# nintendac_mini.net
KiCad netlist of a schematic drawn in EAGLE
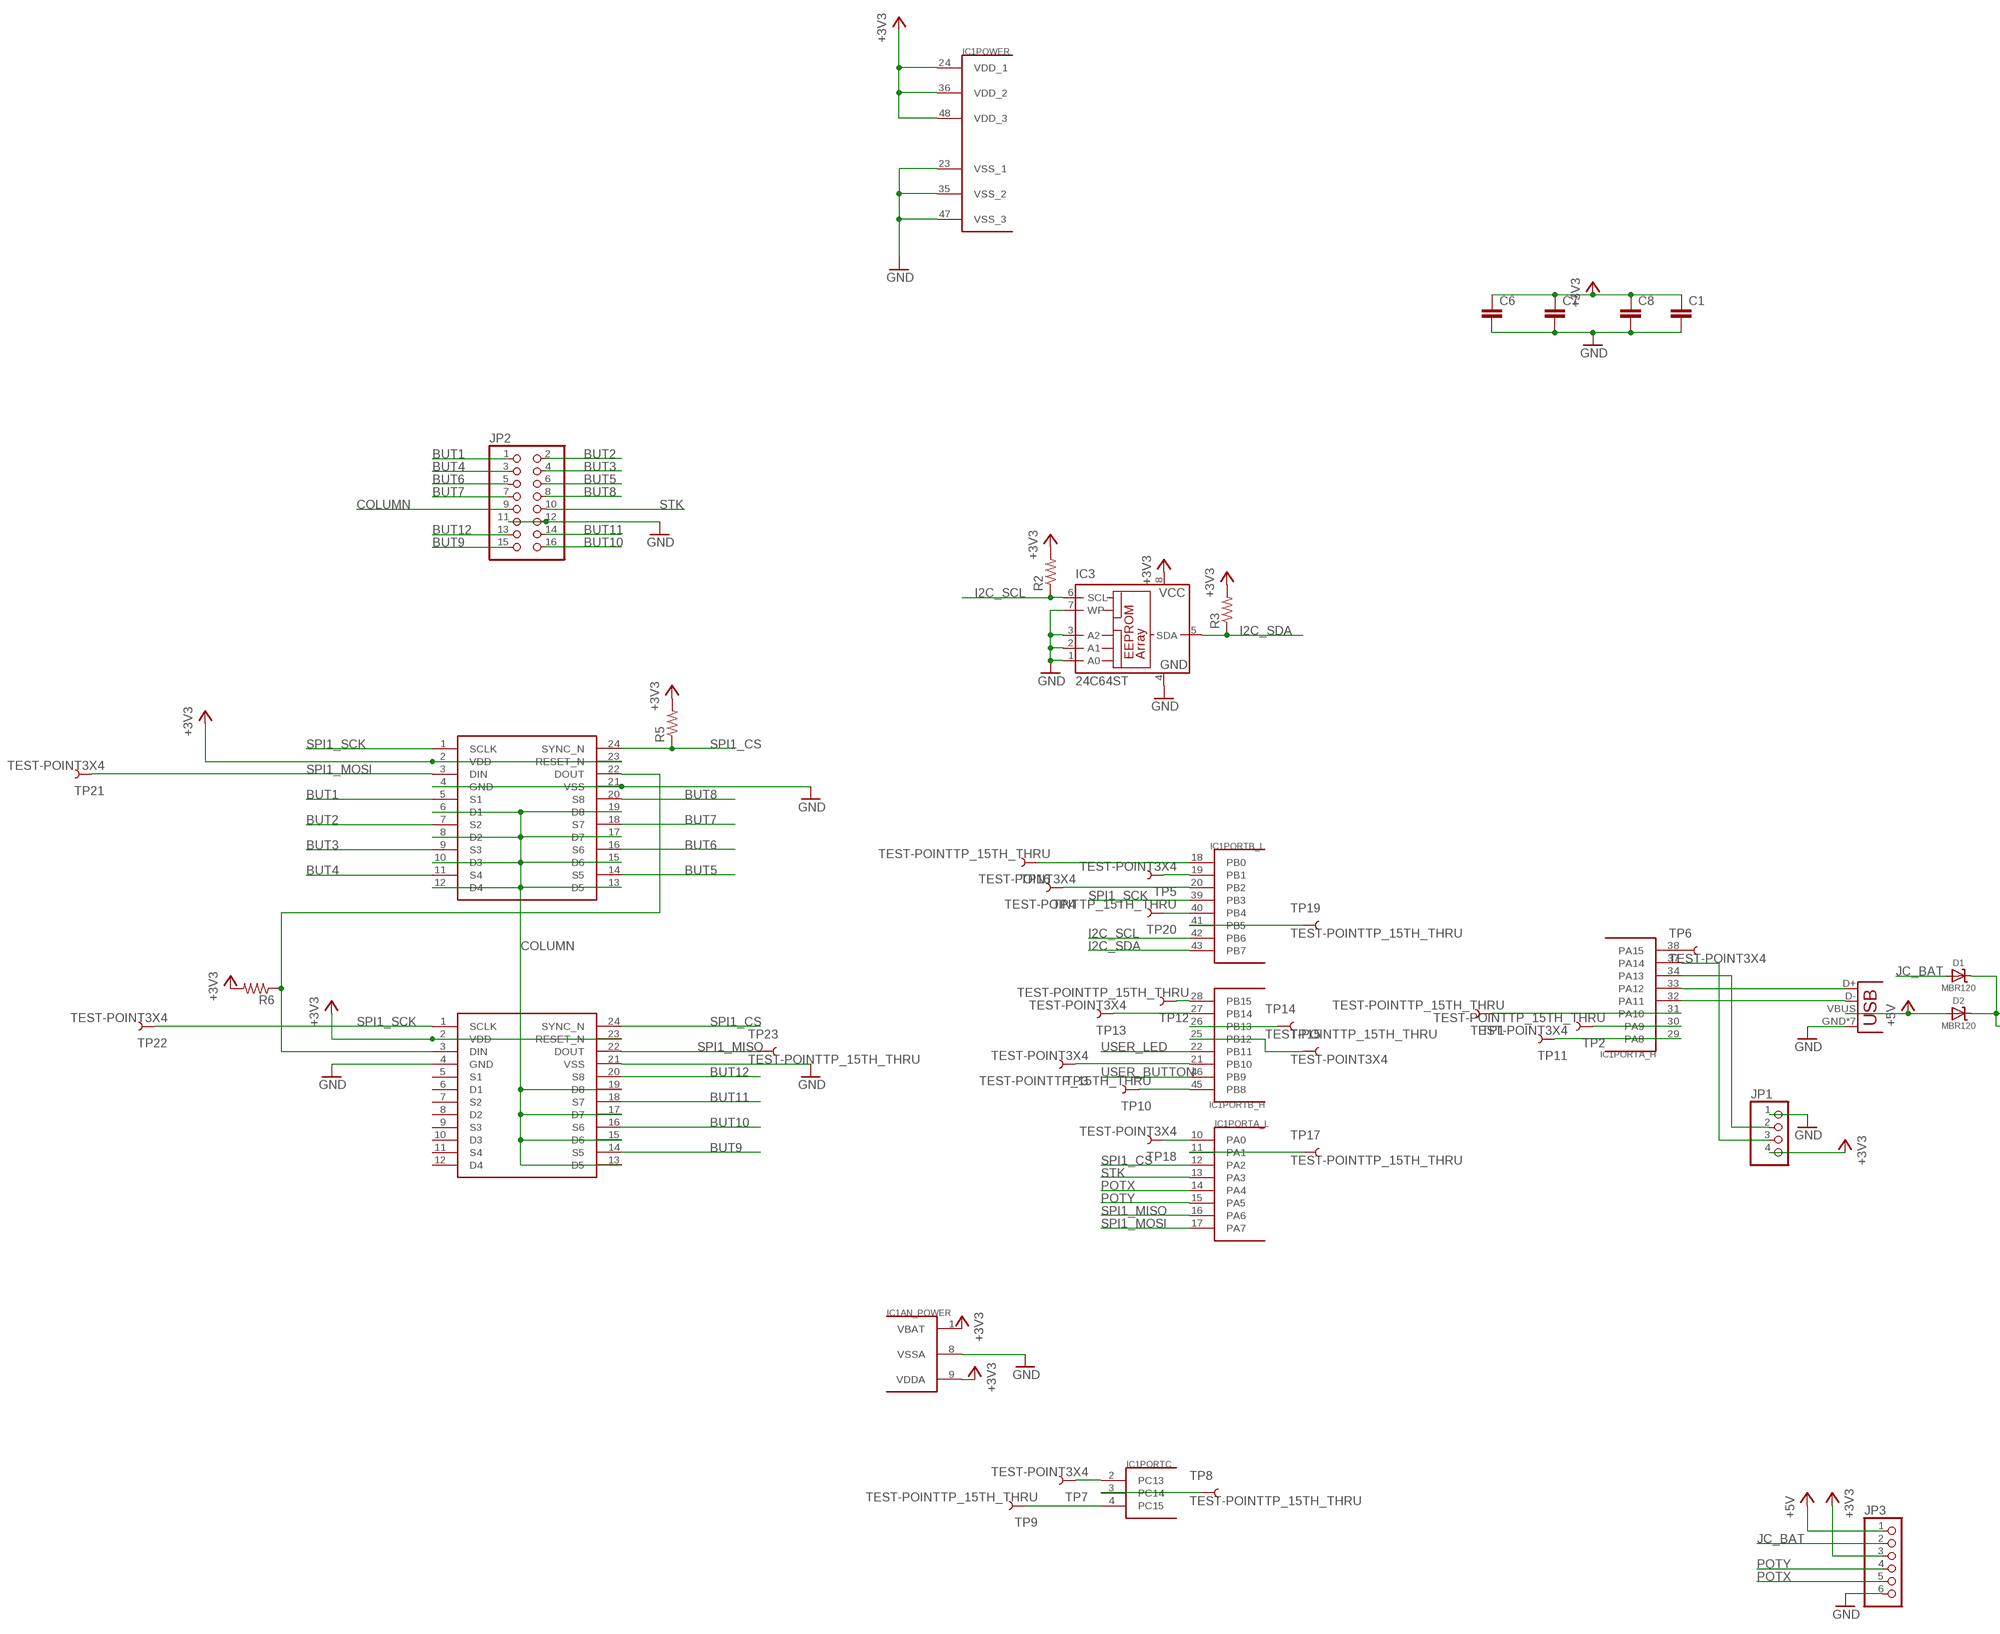
[diagram p0: schematic, sheet 1, part 1 of 2]
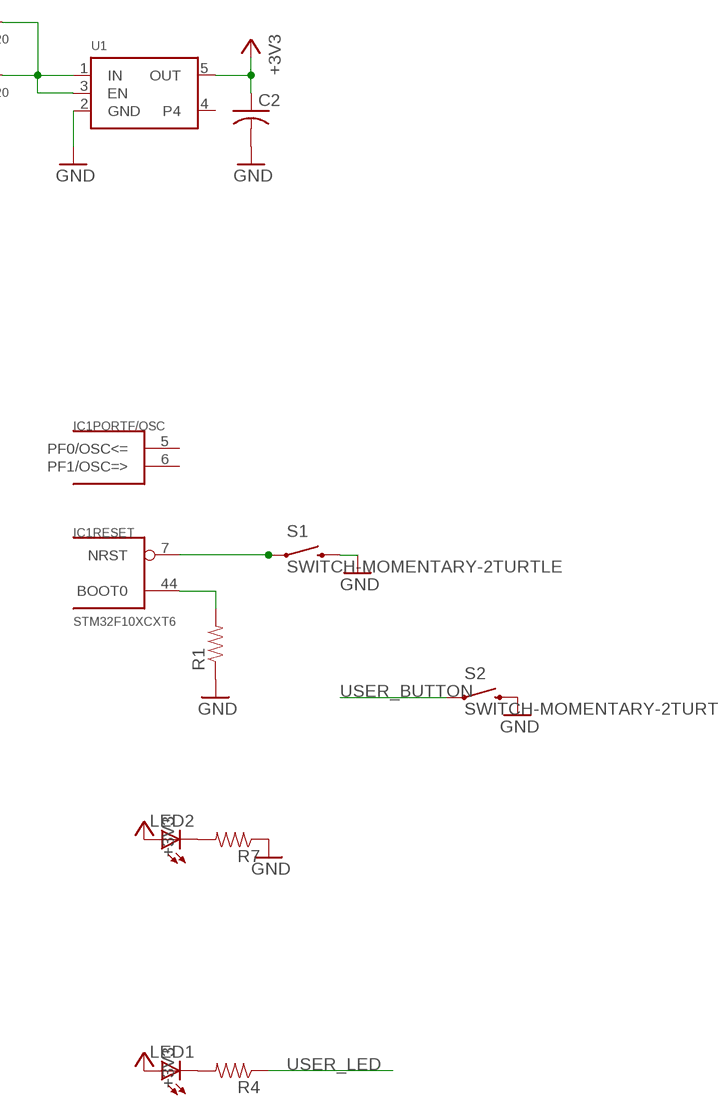
[diagram p1: schematic, sheet 1, part 2 of 2]

(export (version "E")
  (design (tool "Eeschema 10.0.6"))
  (components
    (comp (ref "C1")
      (value "CAP0805")
      (footprint "eagle-import:0805")
      (libsource (lib "eagle-import") (part "CAP0805"))
    )
    (comp (ref "C2")
      (value "C-USC1210")
      (footprint "eagle-import:C1210")
      (libsource (lib "eagle-import") (part "C-USC1210"))
    )
    (comp (ref "C6")
      (value "CAP0805")
      (footprint "eagle-import:0805")
      (libsource (lib "eagle-import") (part "CAP0805"))
    )
    (comp (ref "C7")
      (value "CAP0805")
      (footprint "eagle-import:0805")
      (libsource (lib "eagle-import") (part "CAP0805"))
    )
    (comp (ref "C8")
      (value "CAP0805")
      (footprint "eagle-import:0805")
      (libsource (lib "eagle-import") (part "CAP0805"))
    )
    (comp (ref "D1")
      (value "MBR120")
      (footprint "eagle-import:SOD-123")
      (libsource (lib "eagle-import") (part "DIODE-SCHOTTKYSOD-123"))
    )
    (comp (ref "D2")
      (value "MBR120")
      (footprint "eagle-import:SOD-123")
      (libsource (lib "eagle-import") (part "DIODE-SCHOTTKYSOD-123"))
    )
    (comp (ref "IC1")
      (value "STM32F10XCXT6")
      (footprint "eagle-import:TQFP48")
      (libsource (lib "eagle-import") (part "STM32F10XCXT6"))
    )
    (comp (ref "IC3")
      (value "24C64ST")
      (footprint "eagle-import:TSSOP8")
      (fields (field (name "MPN") "CAT24C64YI-GT3"))
      (libsource (lib "eagle-import") (part "24STC64"))
    )
    (comp (ref "JP1")
      (value "PINHD-1X4")
      (footprint "eagle-import:1X04")
      (libsource (lib "eagle-import") (part "PINHD-1X4"))
    )
    (comp (ref "JP2")
      (value "PINHD-2X8")
      (footprint "eagle-import:2X08")
      (libsource (lib "eagle-import") (part "PINHD-2X8"))
    )
    (comp (ref "JP3")
      (value "PINHD-1X6CB")
      (footprint "eagle-import:1X06-CLEANBIG")
      (libsource (lib "eagle-import") (part "PINHD-1X6CB"))
    )
    (comp (ref "LED1")
      (value "LEDCHIP-LED0805")
      (footprint "eagle-import:CHIP-LED0805")
      (libsource (lib "eagle-import") (part "LEDCHIP-LED0805"))
    )
    (comp (ref "LED2")
      (value "LEDCHIP-LED0805")
      (footprint "eagle-import:CHIP-LED0805")
      (libsource (lib "eagle-import") (part "LEDCHIP-LED0805"))
    )
    (comp (ref "R1")
      (value "RESISTOR0805-RES")
      (footprint "eagle-import:0805")
      (libsource (lib "eagle-import") (part "RESISTOR0805-RES"))
    )
    (comp (ref "R2")
      (value "RESISTOR0805-RES")
      (footprint "eagle-import:0805")
      (libsource (lib "eagle-import") (part "RESISTOR0805-RES"))
    )
    (comp (ref "R3")
      (value "RESISTOR0805-RES")
      (footprint "eagle-import:0805")
      (libsource (lib "eagle-import") (part "RESISTOR0805-RES"))
    )
    (comp (ref "R4")
      (value "RESISTOR0805-RES")
      (footprint "eagle-import:0805")
      (libsource (lib "eagle-import") (part "RESISTOR0805-RES"))
    )
    (comp (ref "R5")
      (value "RESISTOR0805-RES")
      (footprint "eagle-import:0805")
      (libsource (lib "eagle-import") (part "RESISTOR0805-RES"))
    )
    (comp (ref "R6")
      (value "RESISTOR0805-RES")
      (footprint "eagle-import:0805")
      (libsource (lib "eagle-import") (part "RESISTOR0805-RES"))
    )
    (comp (ref "R7")
      (value "RESISTOR0805-RES")
      (footprint "eagle-import:0805")
      (libsource (lib "eagle-import") (part "RESISTOR0805-RES"))
    )
    (comp (ref "S1")
      (value "SWITCH-MOMENTARY-2TURTLE")
      (footprint "eagle-import:KMR2")
      (libsource (lib "eagle-import") (part "SWITCH-MOMENTARY-2TURTLE"))
    )
    (comp (ref "S2")
      (value "SWITCH-MOMENTARY-2TURTLE")
      (footprint "eagle-import:KMR2")
      (libsource (lib "eagle-import") (part "SWITCH-MOMENTARY-2TURTLE"))
    )
    (comp (ref "TP1")
      (value "TEST-POINTTP_15TH_THRU")
      (footprint "eagle-import:TP_15TH")
      (libsource (lib "eagle-import") (part "pth testpoint_TEST-POINTTP_15TH_THRU"))
    )
    (comp (ref "TP2")
      (value "TEST-POINTTP_15TH_THRU")
      (footprint "eagle-import:TP_15TH")
      (libsource (lib "eagle-import") (part "pth testpoint_TEST-POINTTP_15TH_THRU"))
    )
    (comp (ref "TP3")
      (value "TEST-POINT3X4")
      (footprint "eagle-import:PAD.03X.04")
      (libsource (lib "eagle-import") (part "TEST-POINT3X4"))
    )
    (comp (ref "TP4")
      (value "TEST-POINT3X4")
      (footprint "eagle-import:PAD.03X.04")
      (libsource (lib "eagle-import") (part "TEST-POINT3X4"))
    )
    (comp (ref "TP5")
      (value "TEST-POINT3X4")
      (footprint "eagle-import:PAD.03X.04")
      (libsource (lib "eagle-import") (part "TEST-POINT3X4"))
    )
    (comp (ref "TP6")
      (value "TEST-POINT3X4")
      (footprint "eagle-import:PAD.03X.04")
      (libsource (lib "eagle-import") (part "TEST-POINT3X4"))
    )
    (comp (ref "TP7")
      (value "TEST-POINT3X4")
      (footprint "eagle-import:PAD.03X.04")
      (libsource (lib "eagle-import") (part "TEST-POINT3X4"))
    )
    (comp (ref "TP8")
      (value "TEST-POINTTP_15TH_THRU")
      (footprint "eagle-import:TP_15TH")
      (libsource (lib "eagle-import") (part "pth testpoint_TEST-POINTTP_15TH_THRU"))
    )
    (comp (ref "TP9")
      (value "TEST-POINTTP_15TH_THRU")
      (footprint "eagle-import:TP_15TH")
      (libsource (lib "eagle-import") (part "pth testpoint_TEST-POINTTP_15TH_THRU"))
    )
    (comp (ref "TP10")
      (value "TEST-POINTTP_15TH_THRU")
      (footprint "eagle-import:TP_15TH")
      (libsource (lib "eagle-import") (part "pth testpoint_TEST-POINTTP_15TH_THRU"))
    )
    (comp (ref "TP11")
      (value "TEST-POINT3X4")
      (footprint "eagle-import:PAD.03X.04")
      (libsource (lib "eagle-import") (part "TEST-POINT3X4"))
    )
    (comp (ref "TP12")
      (value "TEST-POINTTP_15TH_THRU")
      (footprint "eagle-import:TP_15TH")
      (libsource (lib "eagle-import") (part "pth testpoint_TEST-POINTTP_15TH_THRU"))
    )
    (comp (ref "TP13")
      (value "TEST-POINT3X4")
      (footprint "eagle-import:PAD.03X.04")
      (libsource (lib "eagle-import") (part "TEST-POINT3X4"))
    )
    (comp (ref "TP14")
      (value "TEST-POINTTP_15TH_THRU")
      (footprint "eagle-import:TP_15TH")
      (libsource (lib "eagle-import") (part "pth testpoint_TEST-POINTTP_15TH_THRU"))
    )
    (comp (ref "TP15")
      (value "TEST-POINT3X4")
      (footprint "eagle-import:PAD.03X.04")
      (libsource (lib "eagle-import") (part "TEST-POINT3X4"))
    )
    (comp (ref "TP16")
      (value "TEST-POINTTP_15TH_THRU")
      (footprint "eagle-import:TP_15TH")
      (libsource (lib "eagle-import") (part "pth testpoint_TEST-POINTTP_15TH_THRU"))
    )
    (comp (ref "TP17")
      (value "TEST-POINTTP_15TH_THRU")
      (footprint "eagle-import:TP_15TH")
      (libsource (lib "eagle-import") (part "pth testpoint_TEST-POINTTP_15TH_THRU"))
    )
    (comp (ref "TP18")
      (value "TEST-POINT3X4")
      (footprint "eagle-import:PAD.03X.04")
      (libsource (lib "eagle-import") (part "TEST-POINT3X4"))
    )
    (comp (ref "TP19")
      (value "TEST-POINTTP_15TH_THRU")
      (footprint "eagle-import:TP_15TH")
      (libsource (lib "eagle-import") (part "pth testpoint_TEST-POINTTP_15TH_THRU"))
    )
    (comp (ref "TP20")
      (value "TEST-POINTTP_15TH_THRU")
      (footprint "eagle-import:TP_15TH")
      (libsource (lib "eagle-import") (part "pth testpoint_TEST-POINTTP_15TH_THRU"))
    )
    (comp (ref "TP21")
      (value "TEST-POINT3X4")
      (footprint "eagle-import:PAD.03X.04")
      (libsource (lib "eagle-import") (part "TEST-POINT3X4"))
    )
    (comp (ref "TP22")
      (value "TEST-POINT3X4")
      (footprint "eagle-import:PAD.03X.04")
      (libsource (lib "eagle-import") (part "TEST-POINT3X4"))
    )
    (comp (ref "TP23")
      (value "TEST-POINTTP_15TH_THRU")
      (footprint "eagle-import:TP_15TH")
      (libsource (lib "eagle-import") (part "pth testpoint_TEST-POINTTP_15TH_THRU"))
    )
    (comp (ref "U$3")
      (value "ADG714_DEV")
      (footprint "eagle-import:TSSOP-24")
      (libsource (lib "eagle-import") (part "ADG714_DEV"))
    )
    (comp (ref "U$4")
      (value "ADG714_DEV")
      (footprint "eagle-import:TSSOP-24")
      (libsource (lib "eagle-import") (part "ADG714_DEV"))
    )
    (comp (ref "U1")
      (value "VREG_SOT23-5")
      (footprint "eagle-import:SOT23-5")
      (libsource (lib "eagle-import") (part "VREG_SOT23-5"))
    )
    (comp (ref "X1")
      (value "USB-MICROB")
      (footprint "eagle-import:USB-MICROB")
      (libsource (lib "eagle-import") (part "USB-MICROB"))
    )
  )
  (nets
    (net (code "1") (name "+3V3") (class "Default")
      (node (ref "C1") (pin "1") (pinfunction "1_1") (pintype "passive"))
      (node (ref "C2") (pin "1") (pinfunction "1_1") (pintype "passive"))
      (node (ref "C6") (pin "1") (pinfunction "1_1") (pintype "passive"))
      (node (ref "C7") (pin "1") (pinfunction "1_1") (pintype "passive"))
      (node (ref "C8") (pin "1") (pinfunction "1_1") (pintype "passive"))
      (node (ref "IC1") (pin "1") (pinfunction "VBAT_1") (pintype "power_in"))
      (node (ref "IC1") (pin "24") (pinfunction "VDD_1_24") (pintype "power_in"))
      (node (ref "IC1") (pin "36") (pinfunction "VDD_2_36") (pintype "power_in"))
      (node (ref "IC1") (pin "48") (pinfunction "VDD_3_48") (pintype "power_in"))
      (node (ref "IC1") (pin "9") (pinfunction "VDDA_9") (pintype "power_in"))
      (node (ref "IC3") (pin "8") (pinfunction "VCC_8") (pintype "power_in"))
      (node (ref "JP1") (pin "4") (pinfunction "4_4") (pintype "passive"))
      (node (ref "JP3") (pin "3") (pinfunction "3_3") (pintype "passive"))
      (node (ref "LED1") (pin "A") (pinfunction "A_A") (pintype "passive"))
      (node (ref "LED2") (pin "A") (pinfunction "A_A") (pintype "passive"))
      (node (ref "R2") (pin "2") (pinfunction "2_2") (pintype "passive"))
      (node (ref "R3") (pin "2") (pinfunction "2_2") (pintype "passive"))
      (node (ref "R5") (pin "2") (pinfunction "2_2") (pintype "passive"))
      (node (ref "R6") (pin "2") (pinfunction "2_2") (pintype "passive"))
      (node (ref "U$3") (pin "2") (pinfunction "VDD_2") (pintype "bidirectional"))
      (node (ref "U$3") (pin "23") (pinfunction "RESET_N_23") (pintype "bidirectional"))
      (node (ref "U$4") (pin "2") (pinfunction "VDD_2") (pintype "bidirectional"))
      (node (ref "U$4") (pin "23") (pinfunction "RESET_N_23") (pintype "bidirectional"))
      (node (ref "U1") (pin "5") (pinfunction "OUT_5") (pintype "power_in"))
    )
    (net (code "2") (name "+5V") (class "Default")
      (node (ref "D2") (pin "A") (pinfunction "A_A") (pintype "passive"))
      (node (ref "JP3") (pin "1") (pinfunction "1_1") (pintype "passive"))
      (node (ref "X1") (pin "VBUS") (pinfunction "VBUS_VBUS") (pintype "bidirectional"))
    )
    (net (code "3") (name "/BUT1") (class "Default")
      (node (ref "JP2") (pin "1") (pinfunction "1_1") (pintype "passive"))
      (node (ref "U$3") (pin "5") (pinfunction "S1_5") (pintype "bidirectional"))
    )
    (net (code "4") (name "/BUT2") (class "Default")
      (node (ref "JP2") (pin "2") (pinfunction "2_2") (pintype "passive"))
      (node (ref "U$3") (pin "7") (pinfunction "S2_7") (pintype "bidirectional"))
    )
    (net (code "5") (name "/BUT3") (class "Default")
      (node (ref "JP2") (pin "4") (pinfunction "4_4") (pintype "passive"))
      (node (ref "U$3") (pin "9") (pinfunction "S3_9") (pintype "bidirectional"))
    )
    (net (code "6") (name "/BUT4") (class "Default")
      (node (ref "JP2") (pin "3") (pinfunction "3_3") (pintype "passive"))
      (node (ref "U$3") (pin "11") (pinfunction "S4_11") (pintype "bidirectional"))
    )
    (net (code "7") (name "/BUT5") (class "Default")
      (node (ref "JP2") (pin "6") (pinfunction "6_6") (pintype "passive"))
      (node (ref "U$3") (pin "14") (pinfunction "S5_14") (pintype "bidirectional"))
    )
    (net (code "8") (name "/BUT6") (class "Default")
      (node (ref "JP2") (pin "5") (pinfunction "5_5") (pintype "passive"))
      (node (ref "U$3") (pin "16") (pinfunction "S6_16") (pintype "bidirectional"))
    )
    (net (code "9") (name "/BUT7") (class "Default")
      (node (ref "JP2") (pin "7") (pinfunction "7_7") (pintype "passive"))
      (node (ref "U$3") (pin "18") (pinfunction "S7_18") (pintype "bidirectional"))
    )
    (net (code "10") (name "/BUT8") (class "Default")
      (node (ref "JP2") (pin "8") (pinfunction "8_8") (pintype "passive"))
      (node (ref "U$3") (pin "20") (pinfunction "S8_20") (pintype "bidirectional"))
    )
    (net (code "11") (name "/BUT9") (class "Default")
      (node (ref "JP2") (pin "15") (pinfunction "15_15") (pintype "passive"))
      (node (ref "U$4") (pin "14") (pinfunction "S5_14") (pintype "bidirectional"))
    )
    (net (code "12") (name "/BUT10") (class "Default")
      (node (ref "JP2") (pin "16") (pinfunction "16_16") (pintype "passive"))
      (node (ref "U$4") (pin "16") (pinfunction "S6_16") (pintype "bidirectional"))
    )
    (net (code "13") (name "/BUT11") (class "Default")
      (node (ref "JP2") (pin "14") (pinfunction "14_14") (pintype "passive"))
      (node (ref "U$4") (pin "18") (pinfunction "S7_18") (pintype "bidirectional"))
    )
    (net (code "14") (name "/BUT12") (class "Default")
      (node (ref "JP2") (pin "13") (pinfunction "13_13") (pintype "passive"))
      (node (ref "U$4") (pin "20") (pinfunction "S8_20") (pintype "bidirectional"))
    )
    (net (code "15") (name "/COLUMN") (class "Default")
      (node (ref "JP2") (pin "9") (pinfunction "9_9") (pintype "passive"))
      (node (ref "U$3") (pin "10") (pinfunction "D3_10") (pintype "bidirectional"))
      (node (ref "U$3") (pin "12") (pinfunction "D4_12") (pintype "bidirectional"))
      (node (ref "U$3") (pin "13") (pinfunction "D5_13") (pintype "bidirectional"))
      (node (ref "U$3") (pin "15") (pinfunction "D6_15") (pintype "bidirectional"))
      (node (ref "U$3") (pin "17") (pinfunction "D7_17") (pintype "bidirectional"))
      (node (ref "U$3") (pin "19") (pinfunction "D8_19") (pintype "bidirectional"))
      (node (ref "U$3") (pin "6") (pinfunction "D1_6") (pintype "bidirectional"))
      (node (ref "U$3") (pin "8") (pinfunction "D2_8") (pintype "bidirectional"))
      (node (ref "U$4") (pin "13") (pinfunction "D5_13") (pintype "bidirectional"))
      (node (ref "U$4") (pin "15") (pinfunction "D6_15") (pintype "bidirectional"))
      (node (ref "U$4") (pin "17") (pinfunction "D7_17") (pintype "bidirectional"))
      (node (ref "U$4") (pin "19") (pinfunction "D8_19") (pintype "bidirectional"))
    )
    (net (code "16") (name "/I2C_SCL") (class "Default")
      (node (ref "IC1") (pin "42") (pinfunction "PB6_42") (pintype "bidirectional"))
      (node (ref "IC3") (pin "6") (pinfunction "SCL_6") (pintype "input"))
      (node (ref "R2") (pin "1") (pinfunction "1_1") (pintype "passive"))
    )
    (net (code "17") (name "/I2C_SDA") (class "Default")
      (node (ref "IC1") (pin "43") (pinfunction "PB7_43") (pintype "bidirectional"))
      (node (ref "IC3") (pin "5") (pinfunction "SDA_5") (pintype "bidirectional"))
      (node (ref "R3") (pin "1") (pinfunction "1_1") (pintype "passive"))
    )
    (net (code "18") (name "/JC_BAT") (class "Default")
      (node (ref "D1") (pin "A") (pinfunction "A_A") (pintype "passive"))
      (node (ref "JP3") (pin "2") (pinfunction "2_2") (pintype "passive"))
    )
    (net (code "19") (name "/POTX") (class "Default")
      (node (ref "IC1") (pin "14") (pinfunction "PA4_14") (pintype "bidirectional"))
      (node (ref "JP3") (pin "5") (pinfunction "5_5") (pintype "passive"))
    )
    (net (code "20") (name "/POTY") (class "Default")
      (node (ref "IC1") (pin "15") (pinfunction "PA5_15") (pintype "bidirectional"))
      (node (ref "JP3") (pin "4") (pinfunction "4_4") (pintype "passive"))
    )
    (net (code "21") (name "/SPI1_CS") (class "Default")
      (node (ref "IC1") (pin "12") (pinfunction "PA2_12") (pintype "bidirectional"))
      (node (ref "R5") (pin "1") (pinfunction "1_1") (pintype "passive"))
      (node (ref "U$3") (pin "24") (pinfunction "SYNC_N_24") (pintype "bidirectional"))
      (node (ref "U$4") (pin "24") (pinfunction "SYNC_N_24") (pintype "bidirectional"))
    )
    (net (code "22") (name "/SPI1_MISO") (class "Default")
      (node (ref "IC1") (pin "16") (pinfunction "PA6_16") (pintype "bidirectional"))
      (node (ref "TP23") (pin "P$1") (pinfunction "1_P$1") (pintype "bidirectional"))
      (node (ref "U$4") (pin "22") (pinfunction "DOUT_22") (pintype "bidirectional"))
    )
    (net (code "23") (name "/SPI1_MOSI") (class "Default")
      (node (ref "IC1") (pin "17") (pinfunction "PA7_17") (pintype "bidirectional"))
      (node (ref "TP21") (pin "P$1") (pinfunction "1_P$1") (pintype "bidirectional"))
      (node (ref "U$3") (pin "3") (pinfunction "DIN_3") (pintype "bidirectional"))
    )
    (net (code "24") (name "/SPI1_SCK") (class "Default")
      (node (ref "IC1") (pin "39") (pinfunction "PB3_39") (pintype "bidirectional"))
      (node (ref "TP22") (pin "P$1") (pinfunction "1_P$1") (pintype "bidirectional"))
      (node (ref "U$3") (pin "1") (pinfunction "SCLK_1") (pintype "bidirectional"))
      (node (ref "U$4") (pin "1") (pinfunction "SCLK_1") (pintype "bidirectional"))
    )
    (net (code "25") (name "/STK") (class "Default")
      (node (ref "IC1") (pin "13") (pinfunction "PA3_13") (pintype "bidirectional"))
      (node (ref "JP2") (pin "10") (pinfunction "10_10") (pintype "passive"))
    )
    (net (code "26") (name "/USER_BUTTON") (class "Default")
      (node (ref "IC1") (pin "46") (pinfunction "PB9_46") (pintype "bidirectional"))
      (node (ref "S2") (pin "1") (pinfunction "1_1") (pintype "passive"))
    )
    (net (code "27") (name "/USER_LED") (class "Default")
      (node (ref "IC1") (pin "22") (pinfunction "PB11_22") (pintype "bidirectional"))
      (node (ref "R4") (pin "1") (pinfunction "1_1") (pintype "passive"))
    )
    (net (code "28") (name "GND") (class "Default")
      (node (ref "C1") (pin "2") (pinfunction "2_2") (pintype "passive"))
      (node (ref "C2") (pin "2") (pinfunction "2_2") (pintype "passive"))
      (node (ref "C6") (pin "2") (pinfunction "2_2") (pintype "passive"))
      (node (ref "C7") (pin "2") (pinfunction "2_2") (pintype "passive"))
      (node (ref "C8") (pin "2") (pinfunction "2_2") (pintype "passive"))
      (node (ref "IC1") (pin "23") (pinfunction "VSS_1_23") (pintype "power_in"))
      (node (ref "IC1") (pin "35") (pinfunction "VSS_2_35") (pintype "power_in"))
      (node (ref "IC1") (pin "47") (pinfunction "VSS_3_47") (pintype "power_in"))
      (node (ref "IC1") (pin "8") (pinfunction "VSSA_8") (pintype "power_in"))
      (node (ref "IC3") (pin "1") (pinfunction "A0_1") (pintype "input"))
      (node (ref "IC3") (pin "2") (pinfunction "A1_2") (pintype "input"))
      (node (ref "IC3") (pin "3") (pinfunction "A2_3") (pintype "input"))
      (node (ref "IC3") (pin "4") (pinfunction "GND_4") (pintype "power_in"))
      (node (ref "IC3") (pin "7") (pinfunction "WP_7") (pintype "input"))
      (node (ref "JP1") (pin "1") (pinfunction "1_1") (pintype "passive"))
      (node (ref "JP2") (pin "11") (pinfunction "11_11") (pintype "passive"))
      (node (ref "JP2") (pin "12") (pinfunction "12_12") (pintype "passive"))
      (node (ref "JP3") (pin "6") (pinfunction "6_6") (pintype "passive"))
      (node (ref "R1") (pin "1") (pinfunction "1_1") (pintype "passive"))
      (node (ref "R7") (pin "1") (pinfunction "1_1") (pintype "passive"))
      (node (ref "S1") (pin "3") (pinfunction "2_3") (pintype "passive"))
      (node (ref "S2") (pin "3") (pinfunction "2_3") (pintype "passive"))
      (node (ref "U$3") (pin "21") (pinfunction "VSS_21") (pintype "bidirectional"))
      (node (ref "U$3") (pin "4") (pinfunction "GND_4") (pintype "bidirectional"))
      (node (ref "U$4") (pin "21") (pinfunction "VSS_21") (pintype "bidirectional"))
      (node (ref "U$4") (pin "4") (pinfunction "GND_4") (pintype "bidirectional"))
      (node (ref "U1") (pin "2") (pinfunction "GND_2") (pintype "power_in"))
      (node (ref "X1") (pin "GND") (pinfunction "GND_GND") (pintype "bidirectional"))
      (node (ref "X1") (pin "P1") (pinfunction "GND_P1") (pintype "bidirectional"))
      (node (ref "X1") (pin "P2") (pinfunction "GND_P2") (pintype "bidirectional"))
      (node (ref "X1") (pin "P3") (pinfunction "GND_P3") (pintype "bidirectional"))
      (node (ref "X1") (pin "P4") (pinfunction "GND_P4") (pintype "bidirectional"))
      (node (ref "X1") (pin "P5") (pinfunction "GND_P5") (pintype "bidirectional"))
      (node (ref "X1") (pin "P6") (pinfunction "GND_P6") (pintype "bidirectional"))
    )
    (net (code "29") (name "Net-(IC1B-PA8)") (class "Default")
      (node (ref "IC1") (pin "29") (pinfunction "PA8_29") (pintype "bidirectional"))
      (node (ref "TP11") (pin "P$1") (pinfunction "1_P$1") (pintype "bidirectional"))
    )
    (net (code "30") (name "Net-(IC1B-PA9)") (class "Default")
      (node (ref "IC1") (pin "30") (pinfunction "PA9_30") (pintype "bidirectional"))
      (node (ref "TP2") (pin "P$1") (pinfunction "1_P$1") (pintype "bidirectional"))
    )
    (net (code "31") (name "Net-(IC1B-PA10)") (class "Default")
      (node (ref "IC1") (pin "31") (pinfunction "PA10_31") (pintype "bidirectional"))
      (node (ref "TP1") (pin "P$1") (pinfunction "1_P$1") (pintype "bidirectional"))
    )
    (net (code "32") (name "Net-(IC1B-PA11)") (class "Default")
      (node (ref "IC1") (pin "32") (pinfunction "PA11_32") (pintype "bidirectional"))
      (node (ref "X1") (pin "D-") (pinfunction "D-_D-") (pintype "bidirectional"))
    )
    (net (code "33") (name "Net-(IC1B-PA12)") (class "Default")
      (node (ref "IC1") (pin "33") (pinfunction "PA12_33") (pintype "bidirectional"))
      (node (ref "X1") (pin "D+") (pinfunction "D+_D+") (pintype "bidirectional"))
    )
    (net (code "34") (name "Net-(IC1B-PA13)") (class "Default")
      (node (ref "IC1") (pin "34") (pinfunction "PA13_34") (pintype "bidirectional"))
      (node (ref "JP1") (pin "2") (pinfunction "2_2") (pintype "passive"))
    )
    (net (code "35") (name "Net-(IC1B-PA14)") (class "Default")
      (node (ref "IC1") (pin "37") (pinfunction "PA14_37") (pintype "bidirectional"))
      (node (ref "JP1") (pin "3") (pinfunction "3_3") (pintype "passive"))
    )
    (net (code "36") (name "Net-(IC1B-PA15)") (class "Default")
      (node (ref "IC1") (pin "38") (pinfunction "PA15_38") (pintype "bidirectional"))
      (node (ref "TP6") (pin "P$1") (pinfunction "1_P$1") (pintype "bidirectional"))
    )
    (net (code "37") (name "Net-(IC1C-PA0)") (class "Default")
      (node (ref "IC1") (pin "10") (pinfunction "PA0_10") (pintype "bidirectional"))
      (node (ref "TP18") (pin "P$1") (pinfunction "1_P$1") (pintype "bidirectional"))
    )
    (net (code "38") (name "Net-(IC1C-PA1)") (class "Default")
      (node (ref "IC1") (pin "11") (pinfunction "PA1_11") (pintype "bidirectional"))
      (node (ref "TP17") (pin "P$1") (pinfunction "1_P$1") (pintype "bidirectional"))
    )
    (net (code "39") (name "Net-(IC1D-PB8)") (class "Default")
      (node (ref "IC1") (pin "45") (pinfunction "PB8_45") (pintype "bidirectional"))
      (node (ref "TP10") (pin "P$1") (pinfunction "1_P$1") (pintype "bidirectional"))
    )
    (net (code "40") (name "Net-(IC1D-PB10)") (class "Default")
      (node (ref "IC1") (pin "21") (pinfunction "PB10_21") (pintype "bidirectional"))
      (node (ref "TP3") (pin "P$1") (pinfunction "1_P$1") (pintype "bidirectional"))
    )
    (net (code "41") (name "Net-(IC1D-PB12)") (class "Default")
      (node (ref "IC1") (pin "25") (pinfunction "PB12_25") (pintype "bidirectional"))
      (node (ref "TP15") (pin "P$1") (pinfunction "1_P$1") (pintype "bidirectional"))
    )
    (net (code "42") (name "Net-(IC1D-PB13)") (class "Default")
      (node (ref "IC1") (pin "26") (pinfunction "PB13_26") (pintype "bidirectional"))
      (node (ref "TP14") (pin "P$1") (pinfunction "1_P$1") (pintype "bidirectional"))
    )
    (net (code "43") (name "Net-(IC1D-PB14)") (class "Default")
      (node (ref "IC1") (pin "27") (pinfunction "PB14_27") (pintype "bidirectional"))
      (node (ref "TP13") (pin "P$1") (pinfunction "1_P$1") (pintype "bidirectional"))
    )
    (net (code "44") (name "Net-(IC1D-PB15)") (class "Default")
      (node (ref "IC1") (pin "28") (pinfunction "PB15_28") (pintype "bidirectional"))
      (node (ref "TP12") (pin "P$1") (pinfunction "1_P$1") (pintype "bidirectional"))
    )
    (net (code "45") (name "Net-(IC1E-PB0)") (class "Default")
      (node (ref "IC1") (pin "18") (pinfunction "PB0_18") (pintype "bidirectional"))
      (node (ref "TP16") (pin "P$1") (pinfunction "1_P$1") (pintype "bidirectional"))
    )
    (net (code "46") (name "Net-(IC1E-PB1)") (class "Default")
      (node (ref "IC1") (pin "19") (pinfunction "PB1_19") (pintype "bidirectional"))
      (node (ref "TP5") (pin "P$1") (pinfunction "1_P$1") (pintype "bidirectional"))
    )
    (net (code "47") (name "Net-(IC1E-PB2)") (class "Default")
      (node (ref "IC1") (pin "20") (pinfunction "PB2_20") (pintype "bidirectional"))
      (node (ref "TP4") (pin "P$1") (pinfunction "1_P$1") (pintype "bidirectional"))
    )
    (net (code "48") (name "Net-(IC1E-PB4)") (class "Default")
      (node (ref "IC1") (pin "40") (pinfunction "PB4_40") (pintype "bidirectional"))
      (node (ref "TP20") (pin "P$1") (pinfunction "1_P$1") (pintype "bidirectional"))
    )
    (net (code "49") (name "Net-(IC1E-PB5)") (class "Default")
      (node (ref "IC1") (pin "41") (pinfunction "PB5_41") (pintype "bidirectional"))
      (node (ref "TP19") (pin "P$1") (pinfunction "1_P$1") (pintype "bidirectional"))
    )
    (net (code "50") (name "Net-(IC1F-PC13)") (class "Default")
      (node (ref "IC1") (pin "2") (pinfunction "PC13_2") (pintype "bidirectional"))
      (node (ref "TP7") (pin "P$1") (pinfunction "1_P$1") (pintype "bidirectional"))
    )
    (net (code "51") (name "Net-(IC1F-PC14)") (class "Default")
      (node (ref "IC1") (pin "3") (pinfunction "PC14_3") (pintype "bidirectional"))
      (node (ref "TP8") (pin "P$1") (pinfunction "1_P$1") (pintype "bidirectional"))
    )
    (net (code "52") (name "Net-(IC1F-PC15)") (class "Default")
      (node (ref "IC1") (pin "4") (pinfunction "PC15_4") (pintype "bidirectional"))
      (node (ref "TP9") (pin "P$1") (pinfunction "1_P$1") (pintype "bidirectional"))
    )
    (net (code "53") (name "Net-(IC1I-BOOT0)") (class "Default")
      (node (ref "IC1") (pin "44") (pinfunction "BOOT0_44") (pintype "input"))
      (node (ref "R1") (pin "2") (pinfunction "2_2") (pintype "passive"))
    )
    (net (code "54") (name "Net-(IC1I-NRST)") (class "Default")
      (node (ref "IC1") (pin "7") (pinfunction "NRST_7") (pintype "input"))
      (node (ref "S1") (pin "1") (pinfunction "1_1") (pintype "passive"))
    )
    (net (code "55") (name "Net-(LED1-PadC)") (class "Default")
      (node (ref "LED1") (pin "C") (pinfunction "C_C") (pintype "passive"))
      (node (ref "R4") (pin "2") (pinfunction "2_2") (pintype "passive"))
    )
    (net (code "56") (name "Net-(LED2-PadC)") (class "Default")
      (node (ref "LED2") (pin "C") (pinfunction "C_C") (pintype "passive"))
      (node (ref "R7") (pin "2") (pinfunction "2_2") (pintype "passive"))
    )
    (net (code "57") (name "Net-(U$3-DOUT)") (class "Default")
      (node (ref "R6") (pin "1") (pinfunction "1_1") (pintype "passive"))
      (node (ref "U$3") (pin "22") (pinfunction "DOUT_22") (pintype "bidirectional"))
      (node (ref "U$4") (pin "3") (pinfunction "DIN_3") (pintype "bidirectional"))
    )
    (net (code "58") (name "Net-(U1-EN)") (class "Default")
      (node (ref "D1") (pin "C") (pinfunction "C_C") (pintype "passive"))
      (node (ref "D2") (pin "C") (pinfunction "C_C") (pintype "passive"))
      (node (ref "U1") (pin "1") (pinfunction "IN_1") (pintype "power_in"))
      (node (ref "U1") (pin "3") (pinfunction "EN_3") (pintype "input"))
    )
    (net (code "59") (name "unconnected-(IC1G-PF0{slash}OSC<=-Pad5)") (class "Default")
      (node (ref "IC1") (pin "5") (pinfunction "PF0/OSC<=_5") (pintype "bidirectional"))
    )
    (net (code "60") (name "unconnected-(IC1G-PF1{slash}OSC=>-Pad6)") (class "Default")
      (node (ref "IC1") (pin "6") (pinfunction "PF1/OSC=>_6") (pintype "bidirectional"))
    )
    (net (code "61") (name "unconnected-(U$4-D1-Pad6)") (class "Default")
      (node (ref "U$4") (pin "6") (pinfunction "D1_6") (pintype "bidirectional"))
    )
    (net (code "62") (name "unconnected-(U$4-D2-Pad8)") (class "Default")
      (node (ref "U$4") (pin "8") (pinfunction "D2_8") (pintype "bidirectional"))
    )
    (net (code "63") (name "unconnected-(U$4-D3-Pad10)") (class "Default")
      (node (ref "U$4") (pin "10") (pinfunction "D3_10") (pintype "bidirectional"))
    )
    (net (code "64") (name "unconnected-(U$4-D4-Pad12)") (class "Default")
      (node (ref "U$4") (pin "12") (pinfunction "D4_12") (pintype "bidirectional"))
    )
    (net (code "65") (name "unconnected-(U$4-S1-Pad5)") (class "Default")
      (node (ref "U$4") (pin "5") (pinfunction "S1_5") (pintype "bidirectional"))
    )
    (net (code "66") (name "unconnected-(U$4-S2-Pad7)") (class "Default")
      (node (ref "U$4") (pin "7") (pinfunction "S2_7") (pintype "bidirectional"))
    )
    (net (code "67") (name "unconnected-(U$4-S3-Pad9)") (class "Default")
      (node (ref "U$4") (pin "9") (pinfunction "S3_9") (pintype "bidirectional"))
    )
    (net (code "68") (name "unconnected-(U$4-S4-Pad11)") (class "Default")
      (node (ref "U$4") (pin "11") (pinfunction "S4_11") (pintype "bidirectional"))
    )
    (net (code "69") (name "unconnected-(U1-P4-Pad4)") (class "Default")
      (node (ref "U1") (pin "4") (pinfunction "P4_4") (pintype "bidirectional"))
    )
  )
)
